# 3_VoLTE.net
KiCad netlist of a schematic drawn in Altium Designer
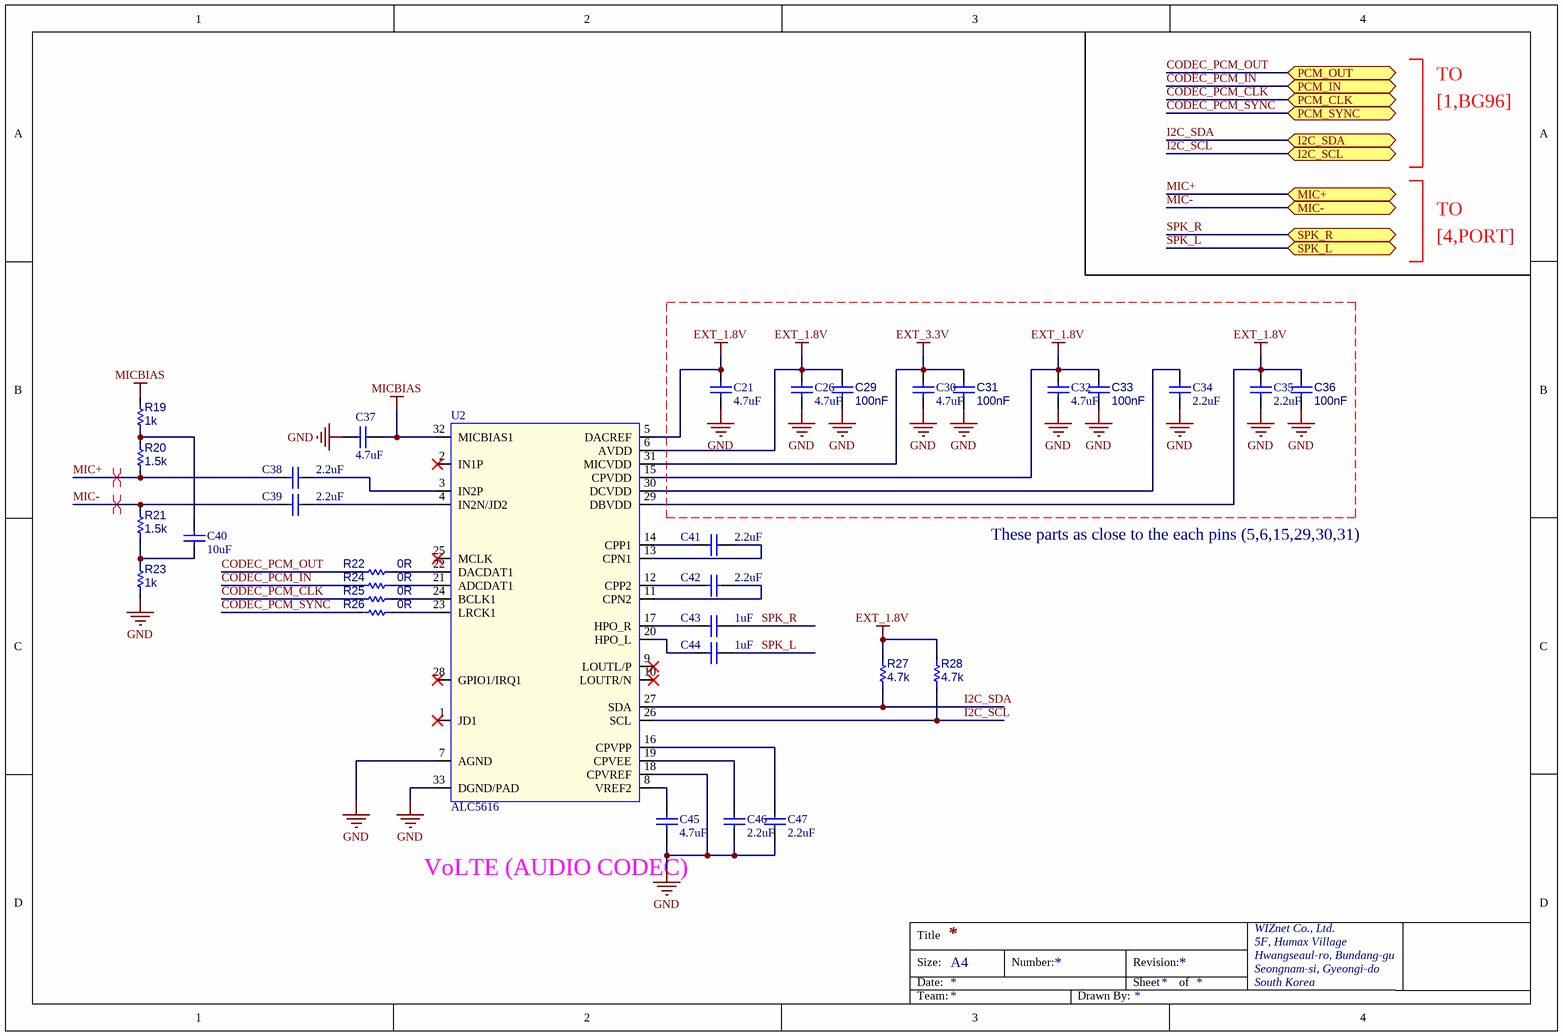
[diagram p0: 3.VoLTE.SchDoc]

(export (version "E")
  (design (tool "Eeschema 10.0.6"))
  (components
    (comp (ref "C21")
      (value "4.7uF")
      (footprint "CAP-0603")
      (description "Ceramic CAP 0603(1608)")
      (libsource (lib "Edward") (part "CAP-0603"))
    )
    (comp (ref "C26")
      (value "4.7uF")
      (footprint "CAP-0603")
      (description "Ceramic CAP 0603(1608)")
      (libsource (lib "Edward") (part "CAP-0603"))
    )
    (comp (ref "C29")
      (value "100nF")
      (footprint "CAP-0402")
      (description "Ceramic CAP 0402(1005)")
      (libsource (lib "Scott_lib") (part "CAP-0402"))
    )
    (comp (ref "C30")
      (value "4.7uF")
      (footprint "CAP-0603")
      (description "Ceramic CAP 0603(1608)")
      (libsource (lib "Edward") (part "CAP-0603"))
    )
    (comp (ref "C31")
      (value "100nF")
      (footprint "CAP-0402")
      (description "Ceramic CAP 0402(1005)")
      (libsource (lib "Scott_lib") (part "CAP-0402"))
    )
    (comp (ref "C32")
      (value "4.7uF")
      (footprint "CAP-0603")
      (description "Ceramic CAP 0603(1608)")
      (libsource (lib "Edward") (part "CAP-0603"))
    )
    (comp (ref "C33")
      (value "100nF")
      (footprint "CAP-0402")
      (description "Ceramic CAP 0402(1005)")
      (libsource (lib "Scott_lib") (part "CAP-0402"))
    )
    (comp (ref "C34")
      (value "2.2uF")
      (footprint "CAP-0603")
      (description "Ceramic CAP 0603(1608)")
      (libsource (lib "Edward") (part "CAP-0603"))
    )
    (comp (ref "C35")
      (value "2.2uF")
      (footprint "CAP-0603")
      (description "Ceramic CAP 0603(1608)")
      (libsource (lib "Edward") (part "CAP-0603"))
    )
    (comp (ref "C36")
      (value "100nF")
      (footprint "CAP-0402")
      (description "Ceramic CAP 0402(1005)")
      (libsource (lib "Scott_lib") (part "CAP-0402"))
    )
    (comp (ref "C37")
      (value "4.7uF")
      (footprint "CAP-0603")
      (description "Ceramic CAP 0603(1608)")
      (libsource (lib "Edward") (part "CAP-0603"))
    )
    (comp (ref "C38")
      (value "2.2uF")
      (footprint "CAP-0603")
      (description "Ceramic CAP 0603(1608)")
      (libsource (lib "Edward") (part "CAP-0603"))
    )
    (comp (ref "C39")
      (value "2.2uF")
      (footprint "CAP-0603")
      (description "Ceramic CAP 0603(1608)")
      (libsource (lib "Edward") (part "CAP-0603"))
    )
    (comp (ref "C40")
      (value "10uF")
      (footprint "CAP-0603")
      (description "Ceramic CAP 0603(1608)")
      (libsource (lib "Edward") (part "CAP-0603"))
    )
    (comp (ref "C41")
      (value "2.2uF")
      (footprint "CAP-0603")
      (description "Ceramic CAP 0603(1608)")
      (libsource (lib "Edward") (part "CAP-0603"))
    )
    (comp (ref "C42")
      (value "2.2uF")
      (footprint "CAP-0603")
      (description "Ceramic CAP 0603(1608)")
      (libsource (lib "Edward") (part "CAP-0603"))
    )
    (comp (ref "C43")
      (value "1uF")
      (footprint "CAP-0603")
      (description "Ceramic CAP 0603(1608)")
      (libsource (lib "Edward") (part "CAP-0603"))
    )
    (comp (ref "C44")
      (value "1uF")
      (footprint "CAP-0603")
      (description "Ceramic CAP 0603(1608)")
      (libsource (lib "Edward") (part "CAP-0603"))
    )
    (comp (ref "C45")
      (value "4.7uF")
      (footprint "CAP-0603")
      (description "Ceramic CAP 0603(1608)")
      (libsource (lib "Edward") (part "CAP-0603"))
    )
    (comp (ref "C46")
      (value "2.2uF")
      (footprint "CAP-0603")
      (description "Ceramic CAP 0603(1608)")
      (libsource (lib "Edward") (part "CAP-0603"))
    )
    (comp (ref "C47")
      (value "2.2uF")
      (footprint "CAP-0603")
      (description "Ceramic CAP 0603(1608)")
      (libsource (lib "Edward") (part "CAP-0603"))
    )
    (comp (ref "R19")
      (value "1k")
      (footprint "RES-0402")
      (description "RES-0402")
      (libsource (lib "Edward") (part "RES-0402"))
    )
    (comp (ref "R20")
      (value "1.5k")
      (footprint "RES-0402")
      (description "RES-0402")
      (libsource (lib "Edward") (part "RES-0402"))
    )
    (comp (ref "R21")
      (value "1.5k")
      (footprint "RES-0402")
      (description "RES-0402")
      (libsource (lib "Edward") (part "RES-0402"))
    )
    (comp (ref "R22")
      (value "0R")
      (footprint "RES-0402")
      (description "RES-0402")
      (libsource (lib "Edward") (part "RES-0402"))
    )
    (comp (ref "R23")
      (value "1k")
      (footprint "RES-0402")
      (description "RES-0402")
      (libsource (lib "Edward") (part "RES-0402"))
    )
    (comp (ref "R24")
      (value "0R")
      (footprint "RES-0402")
      (description "RES-0402")
      (libsource (lib "Edward") (part "RES-0402"))
    )
    (comp (ref "R25")
      (value "0R")
      (footprint "RES-0402")
      (description "RES-0402")
      (libsource (lib "Edward") (part "RES-0402"))
    )
    (comp (ref "R26")
      (value "0R")
      (footprint "RES-0402")
      (description "RES-0402")
      (libsource (lib "Edward") (part "RES-0402"))
    )
    (comp (ref "R27")
      (value "4.7k")
      (footprint "RES-0402")
      (description "RES-0402")
      (libsource (lib "Edward") (part "RES-0402"))
    )
    (comp (ref "R28")
      (value "4.7k")
      (footprint "RES-0402")
      (description "RES-0402")
      (libsource (lib "Edward") (part "RES-0402"))
    )
    (comp (ref "U2")
      (value "ALC5616")
      (footprint "QFN32(0.4/4X4)")
      (description "AUDIO CODEC with QUECTEL VOLTE")
      (libsource (lib "Edward") (part "ALC5616"))
    )
  )
  (nets
    (net (code "1") (name "/CODEC_PCM_CLK") (class "Default")
      (node (ref "R25") (pin "1") (pinfunction "1_1") (pintype "passive"))
    )
    (net (code "2") (name "/CODEC_PCM_IN") (class "Default")
      (node (ref "R24") (pin "1") (pinfunction "1_1") (pintype "passive"))
    )
    (net (code "3") (name "/CODEC_PCM_OUT") (class "Default")
      (node (ref "R22") (pin "1") (pinfunction "1_1") (pintype "passive"))
    )
    (net (code "4") (name "/CODEC_PCM_SYNC") (class "Default")
      (node (ref "R26") (pin "1") (pinfunction "1_1") (pintype "passive"))
    )
    (net (code "5") (name "/I2C_SCL") (class "Default")
      (node (ref "R28") (pin "1") (pinfunction "1_1") (pintype "passive"))
      (node (ref "U2") (pin "26") (pinfunction "SCL_26") (pintype "passive"))
    )
    (net (code "6") (name "/I2C_SDA") (class "Default")
      (node (ref "R27") (pin "1") (pinfunction "1_1") (pintype "passive"))
      (node (ref "U2") (pin "27") (pinfunction "SDA_27") (pintype "passive"))
    )
    (net (code "7") (name "/MIC+") (class "Default")
      (node (ref "C38") (pin "1") (pinfunction "1_1") (pintype "passive"))
      (node (ref "R20") (pin "1") (pinfunction "1_1") (pintype "passive"))
    )
    (net (code "8") (name "/MIC-") (class "Default")
      (node (ref "C39") (pin "1") (pinfunction "1_1") (pintype "passive"))
      (node (ref "R21") (pin "2") (pinfunction "2_2") (pintype "passive"))
    )
    (net (code "9") (name "/SPK_L") (class "Default")
      (node (ref "C44") (pin "2") (pinfunction "2_2") (pintype "passive"))
    )
    (net (code "10") (name "/SPK_R") (class "Default")
      (node (ref "C43") (pin "2") (pinfunction "2_2") (pintype "passive"))
    )
    (net (code "11") (name "EXT_1.8V") (class "Default")
      (node (ref "C21") (pin "2") (pinfunction "2_2") (pintype "passive"))
      (node (ref "C26") (pin "2") (pinfunction "2_2") (pintype "passive"))
      (node (ref "C29") (pin "2") (pinfunction "2_2") (pintype "passive"))
      (node (ref "C32") (pin "2") (pinfunction "2_2") (pintype "passive"))
      (node (ref "C33") (pin "2") (pinfunction "2_2") (pintype "passive"))
      (node (ref "C35") (pin "2") (pinfunction "2_2") (pintype "passive"))
      (node (ref "C36") (pin "2") (pinfunction "2_2") (pintype "passive"))
      (node (ref "R27") (pin "2") (pinfunction "2_2") (pintype "passive"))
      (node (ref "R28") (pin "2") (pinfunction "2_2") (pintype "passive"))
      (node (ref "U2") (pin "15") (pinfunction "CPVDD_15") (pintype "passive"))
      (node (ref "U2") (pin "29") (pinfunction "DBVDD_29") (pintype "passive"))
      (node (ref "U2") (pin "5") (pinfunction "DACREF_5") (pintype "passive"))
      (node (ref "U2") (pin "6") (pinfunction "AVDD_6") (pintype "passive"))
    )
    (net (code "12") (name "EXT_3.3V") (class "Default")
      (node (ref "C30") (pin "2") (pinfunction "2_2") (pintype "passive"))
      (node (ref "C31") (pin "2") (pinfunction "2_2") (pintype "passive"))
      (node (ref "U2") (pin "31") (pinfunction "MICVDD_31") (pintype "passive"))
    )
    (net (code "13") (name "GND") (class "Default")
      (node (ref "C21") (pin "1") (pinfunction "1_1") (pintype "passive"))
      (node (ref "C26") (pin "1") (pinfunction "1_1") (pintype "passive"))
      (node (ref "C29") (pin "1") (pinfunction "1_1") (pintype "passive"))
      (node (ref "C30") (pin "1") (pinfunction "1_1") (pintype "passive"))
      (node (ref "C31") (pin "1") (pinfunction "1_1") (pintype "passive"))
      (node (ref "C32") (pin "1") (pinfunction "1_1") (pintype "passive"))
      (node (ref "C33") (pin "1") (pinfunction "1_1") (pintype "passive"))
      (node (ref "C34") (pin "1") (pinfunction "1_1") (pintype "passive"))
      (node (ref "C35") (pin "1") (pinfunction "1_1") (pintype "passive"))
      (node (ref "C36") (pin "1") (pinfunction "1_1") (pintype "passive"))
      (node (ref "C37") (pin "1") (pinfunction "1_1") (pintype "passive"))
      (node (ref "C45") (pin "1") (pinfunction "1_1") (pintype "passive"))
      (node (ref "C46") (pin "1") (pinfunction "1_1") (pintype "passive"))
      (node (ref "C47") (pin "1") (pinfunction "1_1") (pintype "passive"))
      (node (ref "R23") (pin "1") (pinfunction "1_1") (pintype "passive"))
      (node (ref "U2") (pin "18") (pinfunction "CPVREF_18") (pintype "passive"))
      (node (ref "U2") (pin "33") (pinfunction "DGND/PAD_33") (pintype "passive"))
      (node (ref "U2") (pin "7") (pinfunction "AGND_7") (pintype "passive"))
    )
    (net (code "14") (name "MICBIAS") (class "Default")
      (node (ref "C37") (pin "2") (pinfunction "2_2") (pintype "passive"))
      (node (ref "R19") (pin "2") (pinfunction "2_2") (pintype "passive"))
      (node (ref "U2") (pin "32") (pinfunction "MICBIAS1_32") (pintype "passive"))
    )
    (net (code "15") (name "Net-(C40-Pad1)") (class "Default")
      (node (ref "C40") (pin "1") (pinfunction "1_1") (pintype "passive"))
      (node (ref "R21") (pin "1") (pinfunction "1_1") (pintype "passive"))
      (node (ref "R23") (pin "2") (pinfunction "2_2") (pintype "passive"))
    )
    (net (code "16") (name "Net-(C40-Pad2)") (class "Default")
      (node (ref "C40") (pin "2") (pinfunction "2_2") (pintype "passive"))
      (node (ref "R19") (pin "1") (pinfunction "1_1") (pintype "passive"))
      (node (ref "R20") (pin "2") (pinfunction "2_2") (pintype "passive"))
    )
    (net (code "17") (name "Net-(U2-ADCDAT1)") (class "Default")
      (node (ref "R24") (pin "2") (pinfunction "2_2") (pintype "passive"))
      (node (ref "U2") (pin "21") (pinfunction "ADCDAT1_21") (pintype "passive"))
    )
    (net (code "18") (name "Net-(U2-BCLK1)") (class "Default")
      (node (ref "R25") (pin "2") (pinfunction "2_2") (pintype "passive"))
      (node (ref "U2") (pin "24") (pinfunction "BCLK1_24") (pintype "passive"))
    )
    (net (code "19") (name "Net-(U2-CPN1)") (class "Default")
      (node (ref "C41") (pin "2") (pinfunction "2_2") (pintype "passive"))
      (node (ref "U2") (pin "13") (pinfunction "CPN1_13") (pintype "passive"))
    )
    (net (code "20") (name "Net-(U2-CPN2)") (class "Default")
      (node (ref "C42") (pin "2") (pinfunction "2_2") (pintype "passive"))
      (node (ref "U2") (pin "11") (pinfunction "CPN2_11") (pintype "passive"))
    )
    (net (code "21") (name "Net-(U2-CPP1)") (class "Default")
      (node (ref "C41") (pin "1") (pinfunction "1_1") (pintype "passive"))
      (node (ref "U2") (pin "14") (pinfunction "CPP1_14") (pintype "passive"))
    )
    (net (code "22") (name "Net-(U2-CPP2)") (class "Default")
      (node (ref "C42") (pin "1") (pinfunction "1_1") (pintype "passive"))
      (node (ref "U2") (pin "12") (pinfunction "CPP2_12") (pintype "passive"))
    )
    (net (code "23") (name "Net-(U2-CPVEE)") (class "Default")
      (node (ref "C46") (pin "2") (pinfunction "2_2") (pintype "passive"))
      (node (ref "U2") (pin "19") (pinfunction "CPVEE_19") (pintype "passive"))
    )
    (net (code "24") (name "Net-(U2-CPVPP)") (class "Default")
      (node (ref "C47") (pin "2") (pinfunction "2_2") (pintype "passive"))
      (node (ref "U2") (pin "16") (pinfunction "CPVPP_16") (pintype "passive"))
    )
    (net (code "25") (name "Net-(U2-DACDAT1)") (class "Default")
      (node (ref "R22") (pin "2") (pinfunction "2_2") (pintype "passive"))
      (node (ref "U2") (pin "22") (pinfunction "DACDAT1_22") (pintype "passive"))
    )
    (net (code "26") (name "Net-(U2-DCVDD)") (class "Default")
      (node (ref "C34") (pin "2") (pinfunction "2_2") (pintype "passive"))
      (node (ref "U2") (pin "30") (pinfunction "DCVDD_30") (pintype "passive"))
    )
    (net (code "27") (name "Net-(U2-HPO_L)") (class "Default")
      (node (ref "C44") (pin "1") (pinfunction "1_1") (pintype "passive"))
      (node (ref "U2") (pin "20") (pinfunction "HPO_L_20") (pintype "passive"))
    )
    (net (code "28") (name "Net-(U2-HPO_R)") (class "Default")
      (node (ref "C43") (pin "1") (pinfunction "1_1") (pintype "passive"))
      (node (ref "U2") (pin "17") (pinfunction "HPO_R_17") (pintype "passive"))
    )
    (net (code "29") (name "Net-(U2-IN2N{slash}JD2)") (class "Default")
      (node (ref "C39") (pin "2") (pinfunction "2_2") (pintype "passive"))
      (node (ref "U2") (pin "4") (pinfunction "IN2N/JD2_4") (pintype "passive"))
    )
    (net (code "30") (name "Net-(U2-IN2P)") (class "Default")
      (node (ref "C38") (pin "2") (pinfunction "2_2") (pintype "passive"))
      (node (ref "U2") (pin "3") (pinfunction "IN2P_3") (pintype "passive"))
    )
    (net (code "31") (name "Net-(U2-LRCK1)") (class "Default")
      (node (ref "R26") (pin "2") (pinfunction "2_2") (pintype "passive"))
      (node (ref "U2") (pin "23") (pinfunction "LRCK1_23") (pintype "passive"))
    )
    (net (code "32") (name "Net-(U2-VREF2)") (class "Default")
      (node (ref "C45") (pin "2") (pinfunction "2_2") (pintype "passive"))
      (node (ref "U2") (pin "8") (pinfunction "VREF2_8") (pintype "passive"))
    )
    (net (code "33") (name "unconnected-(U2-GPIO1{slash}IRQ1-Pad28)") (class "Default")
      (node (ref "U2") (pin "28") (pinfunction "GPIO1/IRQ1_28") (pintype "passive+no_connect"))
    )
    (net (code "34") (name "unconnected-(U2-IN1P-Pad2)") (class "Default")
      (node (ref "U2") (pin "2") (pinfunction "IN1P_2") (pintype "passive+no_connect"))
    )
    (net (code "35") (name "unconnected-(U2-JD1-Pad1)") (class "Default")
      (node (ref "U2") (pin "1") (pinfunction "JD1_1") (pintype "passive+no_connect"))
    )
    (net (code "36") (name "unconnected-(U2-LOUTL{slash}P-Pad9)") (class "Default")
      (node (ref "U2") (pin "9") (pinfunction "LOUTL/P_9") (pintype "passive+no_connect"))
    )
    (net (code "37") (name "unconnected-(U2-LOUTR{slash}N-Pad10)") (class "Default")
      (node (ref "U2") (pin "10") (pinfunction "LOUTR/N_10") (pintype "passive+no_connect"))
    )
    (net (code "38") (name "unconnected-(U2-MCLK-Pad25)") (class "Default")
      (node (ref "U2") (pin "25") (pinfunction "MCLK_25") (pintype "passive+no_connect"))
    )
  )
)
